# NoiseMaker.net
KiCad netlist of a schematic drawn in EAGLE
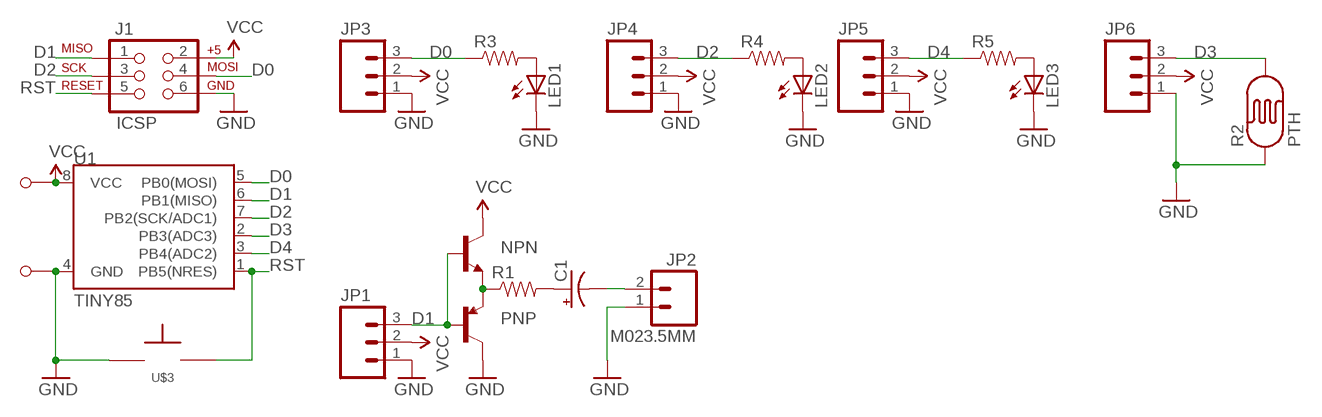
[diagram p0: schematic, sheet 1]

(export (version "E")
  (design (tool "Eeschema 10.0.6"))
  (components
    (comp (ref "C1")
      (value "CAP_POLPTH1")
      (footprint "eagle-import:CPOL-RADIAL-100UF-25V")
      (libsource (lib "eagle-import") (part "CAP_POLPTH1"))
    )
    (comp (ref "J1")
      (value "ICSP")
      (footprint "eagle-import:2X3-NS")
      (libsource (lib "eagle-import") (part "AVR_SPI_PRG_6LABELED"))
    )
    (comp (ref "JP1")
      (value "M03PTH")
      (footprint "eagle-import:1X03")
      (libsource (lib "eagle-import") (part "M03PTH"))
    )
    (comp (ref "JP2")
      (value "M023.5MM")
      (footprint "eagle-import:SCREWTERMINAL-3.5MM-2")
      (libsource (lib "eagle-import") (part "M023.5MM"))
    )
    (comp (ref "JP3")
      (value "M03PTH")
      (footprint "eagle-import:1X03")
      (libsource (lib "eagle-import") (part "M03PTH"))
    )
    (comp (ref "JP4")
      (value "M03PTH")
      (footprint "eagle-import:1X03")
      (libsource (lib "eagle-import") (part "M03PTH"))
    )
    (comp (ref "JP5")
      (value "M03PTH")
      (footprint "eagle-import:1X03")
      (libsource (lib "eagle-import") (part "M03PTH"))
    )
    (comp (ref "JP6")
      (value "M03PTH")
      (footprint "eagle-import:1X03")
      (libsource (lib "eagle-import") (part "M03PTH"))
    )
    (comp (ref "LED1")
      (value "LEDOVAL")
      (footprint "eagle-import:LED-OVAL")
      (libsource (lib "eagle-import") (part "LEDOVAL"))
    )
    (comp (ref "LED2")
      (value "LEDOVAL")
      (footprint "eagle-import:LED-OVAL")
      (libsource (lib "eagle-import") (part "LEDOVAL"))
    )
    (comp (ref "LED3")
      (value "LEDOVAL")
      (footprint "eagle-import:LED-OVAL")
      (libsource (lib "eagle-import") (part "LEDOVAL"))
    )
    (comp (ref "NPN")
      (value "TRANSISTOR_NPNTO-92-AMMO")
      (footprint "eagle-import:TO-92-AMMO")
      (libsource (lib "eagle-import") (part "TRANSISTOR_NPNTO-92-AMMO"))
    )
    (comp (ref "PNP")
      (value "TRANSISTOR_PNPAMMO")
      (footprint "eagle-import:TO-92-AMMO")
      (libsource (lib "eagle-import") (part "TRANSISTOR_PNPAMMO"))
    )
    (comp (ref "R1")
      (value "RESISTORAXIAL-0.3")
      (footprint "eagle-import:AXIAL-0.3")
      (libsource (lib "eagle-import") (part "RESISTORAXIAL-0.3"))
    )
    (comp (ref "R2")
      (value "PTH")
      (footprint "eagle-import:PHOTOCELL")
      (libsource (lib "eagle-import") (part "PHOTOCELLPTH"))
    )
    (comp (ref "R3")
      (value "RESISTORAXIAL-0.3")
      (footprint "eagle-import:AXIAL-0.3")
      (libsource (lib "eagle-import") (part "RESISTORAXIAL-0.3"))
    )
    (comp (ref "R4")
      (value "RESISTORAXIAL-0.3")
      (footprint "eagle-import:AXIAL-0.3")
      (libsource (lib "eagle-import") (part "RESISTORAXIAL-0.3"))
    )
    (comp (ref "R5")
      (value "RESISTORAXIAL-0.3")
      (footprint "eagle-import:AXIAL-0.3")
      (libsource (lib "eagle-import") (part "RESISTORAXIAL-0.3"))
    )
    (comp (ref "U$1")
      (value "M1")
      (footprint "eagle-import:M1_NO_STRAIN")
      (libsource (lib "eagle-import") (part "M1"))
    )
    (comp (ref "U$2")
      (value "M1")
      (footprint "eagle-import:M1_NO_STRAIN")
      (libsource (lib "eagle-import") (part "M1"))
    )
    (comp (ref "U$3")
      (value "TAC_SPST_NO")
      (footprint "eagle-import:TAC_SPST_NO")
      (libsource (lib "eagle-import") (part "TAC_SPST_NO"))
    )
    (comp (ref "U1")
      (value "TINY85")
      (footprint "eagle-import:DIP08")
      (libsource (lib "eagle-import") (part "ATTINY45TINY85-20-DIP"))
    )
  )
  (nets
    (net (code "1") (name "/D0") (class "Default")
      (node (ref "J1") (pin "4") (pinfunction "MOSI_4") (pintype "passive"))
      (node (ref "JP3") (pin "3") (pinfunction "3_3") (pintype "passive"))
      (node (ref "R3") (pin "P$1") (pinfunction "1_P$1") (pintype "passive"))
      (node (ref "U1") (pin "5") (pinfunction "PB0(MOSI)_5") (pintype "bidirectional"))
    )
    (net (code "2") (name "/D1") (class "Default")
      (node (ref "J1") (pin "1") (pinfunction "MISO_1") (pintype "passive"))
      (node (ref "JP1") (pin "3") (pinfunction "3_3") (pintype "passive"))
      (node (ref "NPN") (pin "2") (pinfunction "B_2") (pintype "passive"))
      (node (ref "PNP") (pin "2") (pinfunction "B_2") (pintype "passive"))
      (node (ref "U1") (pin "6") (pinfunction "PB1(MISO)_6") (pintype "bidirectional"))
    )
    (net (code "3") (name "/D2") (class "Default")
      (node (ref "J1") (pin "3") (pinfunction "SCK_3") (pintype "passive"))
      (node (ref "JP4") (pin "3") (pinfunction "3_3") (pintype "passive"))
      (node (ref "R4") (pin "P$1") (pinfunction "1_P$1") (pintype "passive"))
      (node (ref "U1") (pin "7") (pinfunction "PB2(SCK/ADC1)_7") (pintype "bidirectional"))
    )
    (net (code "4") (name "/D3") (class "Default")
      (node (ref "JP6") (pin "3") (pinfunction "3_3") (pintype "passive"))
      (node (ref "R2") (pin "2") (pinfunction "P$2_2") (pintype "bidirectional"))
      (node (ref "U1") (pin "2") (pinfunction "PB3(ADC3)_2") (pintype "bidirectional"))
    )
    (net (code "5") (name "/D4") (class "Default")
      (node (ref "JP5") (pin "3") (pinfunction "3_3") (pintype "passive"))
      (node (ref "R5") (pin "P$1") (pinfunction "1_P$1") (pintype "passive"))
      (node (ref "U1") (pin "3") (pinfunction "PB4(ADC2)_3") (pintype "bidirectional"))
    )
    (net (code "6") (name "/RST") (class "Default")
      (node (ref "J1") (pin "5") (pinfunction "RST_5") (pintype "passive"))
      (node (ref "U$3") (pin "P$2") (pinfunction "P$2_P$2") (pintype "bidirectional"))
      (node (ref "U1") (pin "1") (pinfunction "PB5(NRES)_1") (pintype "bidirectional"))
    )
    (net (code "7") (name "GND") (class "Default")
      (node (ref "J1") (pin "6") (pinfunction "GND_6") (pintype "passive"))
      (node (ref "JP1") (pin "1") (pinfunction "1_1") (pintype "passive"))
      (node (ref "JP2") (pin "1") (pinfunction "1_1") (pintype "passive"))
      (node (ref "JP3") (pin "1") (pinfunction "1_1") (pintype "passive"))
      (node (ref "JP4") (pin "1") (pinfunction "1_1") (pintype "passive"))
      (node (ref "JP5") (pin "1") (pinfunction "1_1") (pintype "passive"))
      (node (ref "JP6") (pin "1") (pinfunction "1_1") (pintype "passive"))
      (node (ref "LED1") (pin "CATHODE") (pinfunction "C_CATHODE") (pintype "passive"))
      (node (ref "LED2") (pin "CATHODE") (pinfunction "C_CATHODE") (pintype "passive"))
      (node (ref "LED3") (pin "CATHODE") (pinfunction "C_CATHODE") (pintype "passive"))
      (node (ref "PNP") (pin "3") (pinfunction "C_3") (pintype "passive"))
      (node (ref "R2") (pin "1") (pinfunction "P$1_1") (pintype "bidirectional"))
      (node (ref "U$2") (pin "P$1") (pinfunction "P$1_P$1") (pintype "bidirectional"))
      (node (ref "U$3") (pin "P$1") (pinfunction "P$1_P$1") (pintype "bidirectional"))
      (node (ref "U1") (pin "4") (pinfunction "GND_4") (pintype "bidirectional"))
    )
    (net (code "8") (name "Net-(C1-+)") (class "Default")
      (node (ref "C1") (pin "1") (pinfunction "+_1") (pintype "passive"))
      (node (ref "R1") (pin "P$2") (pinfunction "2_P$2") (pintype "passive"))
    )
    (net (code "9") (name "Net-(C1--)") (class "Default")
      (node (ref "C1") (pin "2") (pinfunction "-_2") (pintype "passive"))
      (node (ref "JP2") (pin "2") (pinfunction "2_2") (pintype "passive"))
    )
    (net (code "10") (name "Net-(LED1-A)") (class "Default")
      (node (ref "LED1") (pin "ANODE") (pinfunction "A_ANODE") (pintype "passive"))
      (node (ref "R3") (pin "P$2") (pinfunction "2_P$2") (pintype "passive"))
    )
    (net (code "11") (name "Net-(LED2-A)") (class "Default")
      (node (ref "LED2") (pin "ANODE") (pinfunction "A_ANODE") (pintype "passive"))
      (node (ref "R4") (pin "P$2") (pinfunction "2_P$2") (pintype "passive"))
    )
    (net (code "12") (name "Net-(LED3-A)") (class "Default")
      (node (ref "LED3") (pin "ANODE") (pinfunction "A_ANODE") (pintype "passive"))
      (node (ref "R5") (pin "P$2") (pinfunction "2_P$2") (pintype "passive"))
    )
    (net (code "13") (name "Net-(NPN-E)") (class "Default")
      (node (ref "NPN") (pin "1") (pinfunction "E_1") (pintype "passive"))
      (node (ref "PNP") (pin "1") (pinfunction "E_1") (pintype "passive"))
      (node (ref "R1") (pin "P$1") (pinfunction "1_P$1") (pintype "passive"))
    )
    (net (code "14") (name "VCC") (class "Default")
      (node (ref "J1") (pin "2") (pinfunction "V+_2") (pintype "passive"))
      (node (ref "JP1") (pin "2") (pinfunction "2_2") (pintype "passive"))
      (node (ref "JP3") (pin "2") (pinfunction "2_2") (pintype "passive"))
      (node (ref "JP4") (pin "2") (pinfunction "2_2") (pintype "passive"))
      (node (ref "JP5") (pin "2") (pinfunction "2_2") (pintype "passive"))
      (node (ref "JP6") (pin "2") (pinfunction "2_2") (pintype "passive"))
      (node (ref "NPN") (pin "3") (pinfunction "C_3") (pintype "passive"))
      (node (ref "U$1") (pin "P$1") (pinfunction "P$1_P$1") (pintype "bidirectional"))
      (node (ref "U1") (pin "8") (pinfunction "VCC_8") (pintype "bidirectional"))
    )
  )
)
